# Opto_Board.net
KiCad netlist of a schematic drawn in EAGLE
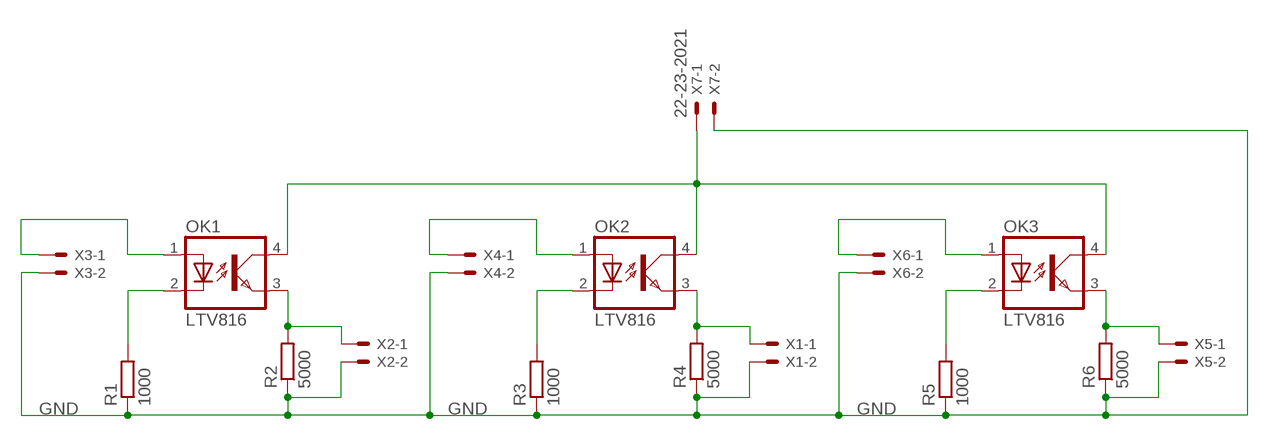
[diagram p0: schematic, sheet 1]

(export (version "E")
  (design (tool "Eeschema 10.0.6"))
  (components
    (comp (ref "OK1")
      (value "LTV816")
      (footprint "eagle-import:DIL04")
      (libsource (lib "eagle-import") (part "LTV816"))
    )
    (comp (ref "OK2")
      (value "LTV816")
      (footprint "eagle-import:DIL04")
      (libsource (lib "eagle-import") (part "LTV816"))
    )
    (comp (ref "OK3")
      (value "LTV816")
      (footprint "eagle-import:DIL04")
      (libsource (lib "eagle-import") (part "LTV816"))
    )
    (comp (ref "R1")
      (value "1000")
      (footprint "eagle-import:0204_7")
      (libsource (lib "eagle-import") (part "R-EU_0204/7"))
    )
    (comp (ref "R2")
      (value "5000")
      (footprint "eagle-import:0204_7")
      (libsource (lib "eagle-import") (part "R-EU_0204/7"))
    )
    (comp (ref "R3")
      (value "1000")
      (footprint "eagle-import:0204_7")
      (libsource (lib "eagle-import") (part "R-EU_0204/7"))
    )
    (comp (ref "R4")
      (value "5000")
      (footprint "eagle-import:0204_7")
      (libsource (lib "eagle-import") (part "R-EU_0204/7"))
    )
    (comp (ref "R5")
      (value "1000")
      (footprint "eagle-import:0204_7")
      (libsource (lib "eagle-import") (part "R-EU_0204/7"))
    )
    (comp (ref "R6")
      (value "5000")
      (footprint "eagle-import:0204_7")
      (libsource (lib "eagle-import") (part "R-EU_0204/7"))
    )
    (comp (ref "X1")
      (value "22-23-2021")
      (footprint "eagle-import:22-23-2021")
      (fields (field (name "MF") "MOLEX"))
      (libsource (lib "eagle-import") (part "22-23-2021"))
    )
    (comp (ref "X2")
      (value "22-23-2021")
      (footprint "eagle-import:22-23-2021")
      (fields (field (name "MF") "MOLEX"))
      (libsource (lib "eagle-import") (part "22-23-2021"))
    )
    (comp (ref "X3")
      (value "22-23-2021")
      (footprint "eagle-import:22-23-2021")
      (fields (field (name "MF") "MOLEX"))
      (libsource (lib "eagle-import") (part "22-23-2021"))
    )
    (comp (ref "X4")
      (value "22-23-2021")
      (footprint "eagle-import:22-23-2021")
      (fields (field (name "MF") "MOLEX"))
      (libsource (lib "eagle-import") (part "22-23-2021"))
    )
    (comp (ref "X5")
      (value "22-23-2021")
      (footprint "eagle-import:22-23-2021")
      (fields (field (name "MF") "MOLEX"))
      (libsource (lib "eagle-import") (part "22-23-2021"))
    )
    (comp (ref "X6")
      (value "22-23-2021")
      (footprint "eagle-import:22-23-2021")
      (fields (field (name "MF") "MOLEX"))
      (libsource (lib "eagle-import") (part "22-23-2021"))
    )
    (comp (ref "X7")
      (value "22-23-2021")
      (footprint "eagle-import:22-23-2021")
      (fields (field (name "MF") "MOLEX"))
      (libsource (lib "eagle-import") (part "22-23-2021"))
    )
  )
  (nets
    (net (code "1") (name "/GND") (class "Default")
      (node (ref "R1") (pin "1") (pinfunction "1_1") (pintype "passive"))
      (node (ref "R2") (pin "1") (pinfunction "1_1") (pintype "passive"))
      (node (ref "R3") (pin "1") (pinfunction "1_1") (pintype "passive"))
      (node (ref "R4") (pin "1") (pinfunction "1_1") (pintype "passive"))
      (node (ref "R5") (pin "1") (pinfunction "1_1") (pintype "passive"))
      (node (ref "R6") (pin "1") (pinfunction "1_1") (pintype "passive"))
      (node (ref "X1") (pin "2") (pinfunction "S_2") (pintype "passive"))
      (node (ref "X2") (pin "2") (pinfunction "S_2") (pintype "passive"))
      (node (ref "X3") (pin "2") (pinfunction "S_2") (pintype "passive"))
      (node (ref "X4") (pin "2") (pinfunction "S_2") (pintype "passive"))
      (node (ref "X5") (pin "2") (pinfunction "S_2") (pintype "passive"))
      (node (ref "X6") (pin "2") (pinfunction "S_2") (pintype "passive"))
      (node (ref "X7") (pin "2") (pinfunction "S_2") (pintype "passive"))
    )
    (net (code "2") (name "Net-(OK1-A)") (class "Default")
      (node (ref "OK1") (pin "1") (pinfunction "A_1") (pintype "passive"))
      (node (ref "X3") (pin "1") (pinfunction "S_1") (pintype "passive"))
    )
    (net (code "3") (name "Net-(OK1-C)") (class "Default")
      (node (ref "OK1") (pin "2") (pinfunction "C_2") (pintype "passive"))
      (node (ref "R1") (pin "2") (pinfunction "2_2") (pintype "passive"))
    )
    (net (code "4") (name "Net-(OK1-COL)") (class "Default")
      (node (ref "OK1") (pin "4") (pinfunction "COL_4") (pintype "passive"))
      (node (ref "OK2") (pin "4") (pinfunction "COL_4") (pintype "passive"))
      (node (ref "OK3") (pin "4") (pinfunction "COL_4") (pintype "passive"))
      (node (ref "X7") (pin "1") (pinfunction "S_1") (pintype "passive"))
    )
    (net (code "5") (name "Net-(OK1-EMIT)") (class "Default")
      (node (ref "OK1") (pin "3") (pinfunction "EMIT_3") (pintype "passive"))
      (node (ref "R2") (pin "2") (pinfunction "2_2") (pintype "passive"))
      (node (ref "X2") (pin "1") (pinfunction "S_1") (pintype "passive"))
    )
    (net (code "6") (name "Net-(OK2-A)") (class "Default")
      (node (ref "OK2") (pin "1") (pinfunction "A_1") (pintype "passive"))
      (node (ref "X4") (pin "1") (pinfunction "S_1") (pintype "passive"))
    )
    (net (code "7") (name "Net-(OK2-C)") (class "Default")
      (node (ref "OK2") (pin "2") (pinfunction "C_2") (pintype "passive"))
      (node (ref "R3") (pin "2") (pinfunction "2_2") (pintype "passive"))
    )
    (net (code "8") (name "Net-(OK2-EMIT)") (class "Default")
      (node (ref "OK2") (pin "3") (pinfunction "EMIT_3") (pintype "passive"))
      (node (ref "R4") (pin "2") (pinfunction "2_2") (pintype "passive"))
      (node (ref "X1") (pin "1") (pinfunction "S_1") (pintype "passive"))
    )
    (net (code "9") (name "Net-(OK3-A)") (class "Default")
      (node (ref "OK3") (pin "1") (pinfunction "A_1") (pintype "passive"))
      (node (ref "X6") (pin "1") (pinfunction "S_1") (pintype "passive"))
    )
    (net (code "10") (name "Net-(OK3-C)") (class "Default")
      (node (ref "OK3") (pin "2") (pinfunction "C_2") (pintype "passive"))
      (node (ref "R5") (pin "2") (pinfunction "2_2") (pintype "passive"))
    )
    (net (code "11") (name "Net-(OK3-EMIT)") (class "Default")
      (node (ref "OK3") (pin "3") (pinfunction "EMIT_3") (pintype "passive"))
      (node (ref "R6") (pin "2") (pinfunction "2_2") (pintype "passive"))
      (node (ref "X5") (pin "1") (pinfunction "S_1") (pintype "passive"))
    )
  )
)
